# RoverWing-V1_1.net
KiCad netlist of a schematic drawn in EAGLE
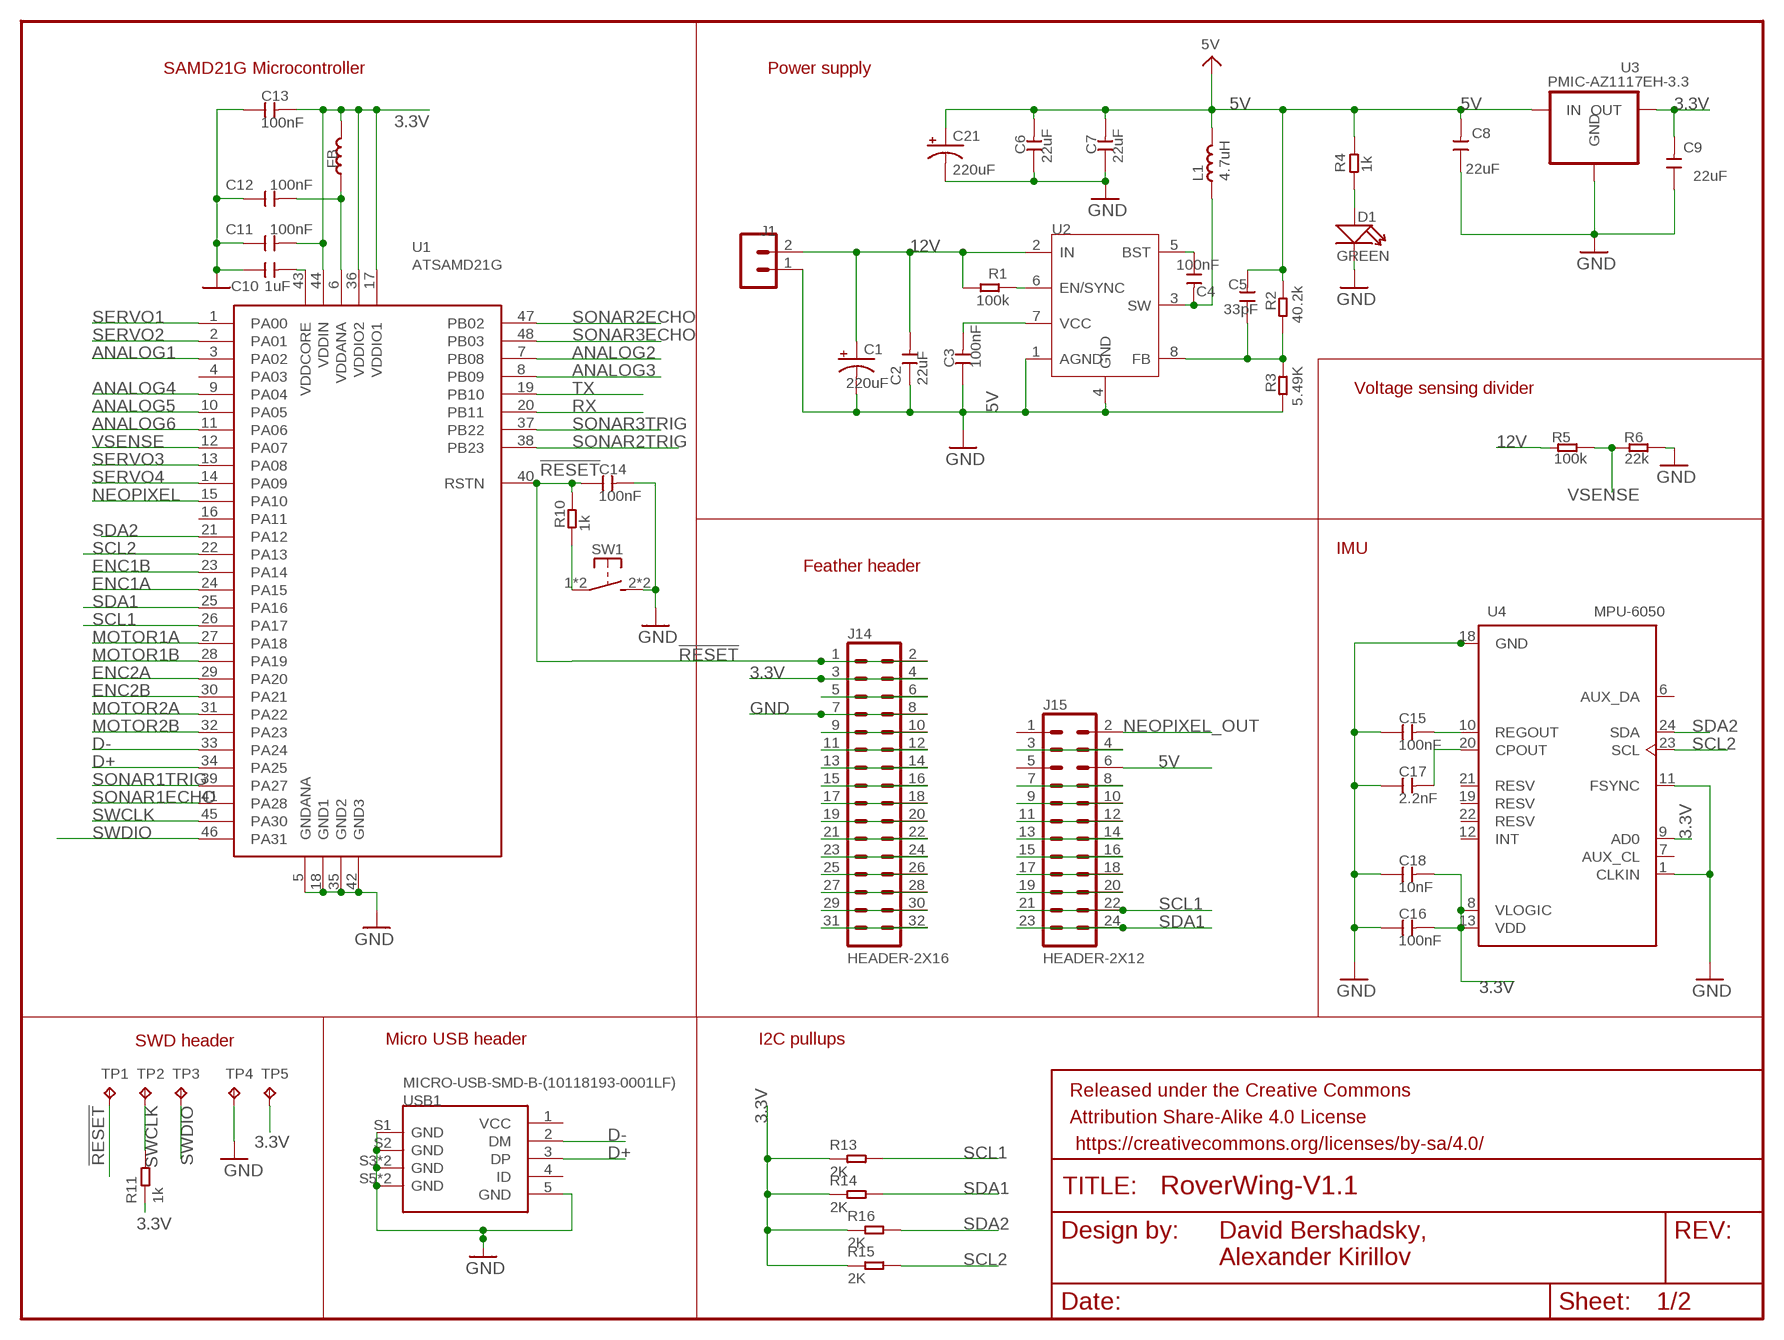
[diagram p0: schematic, sheet 1]
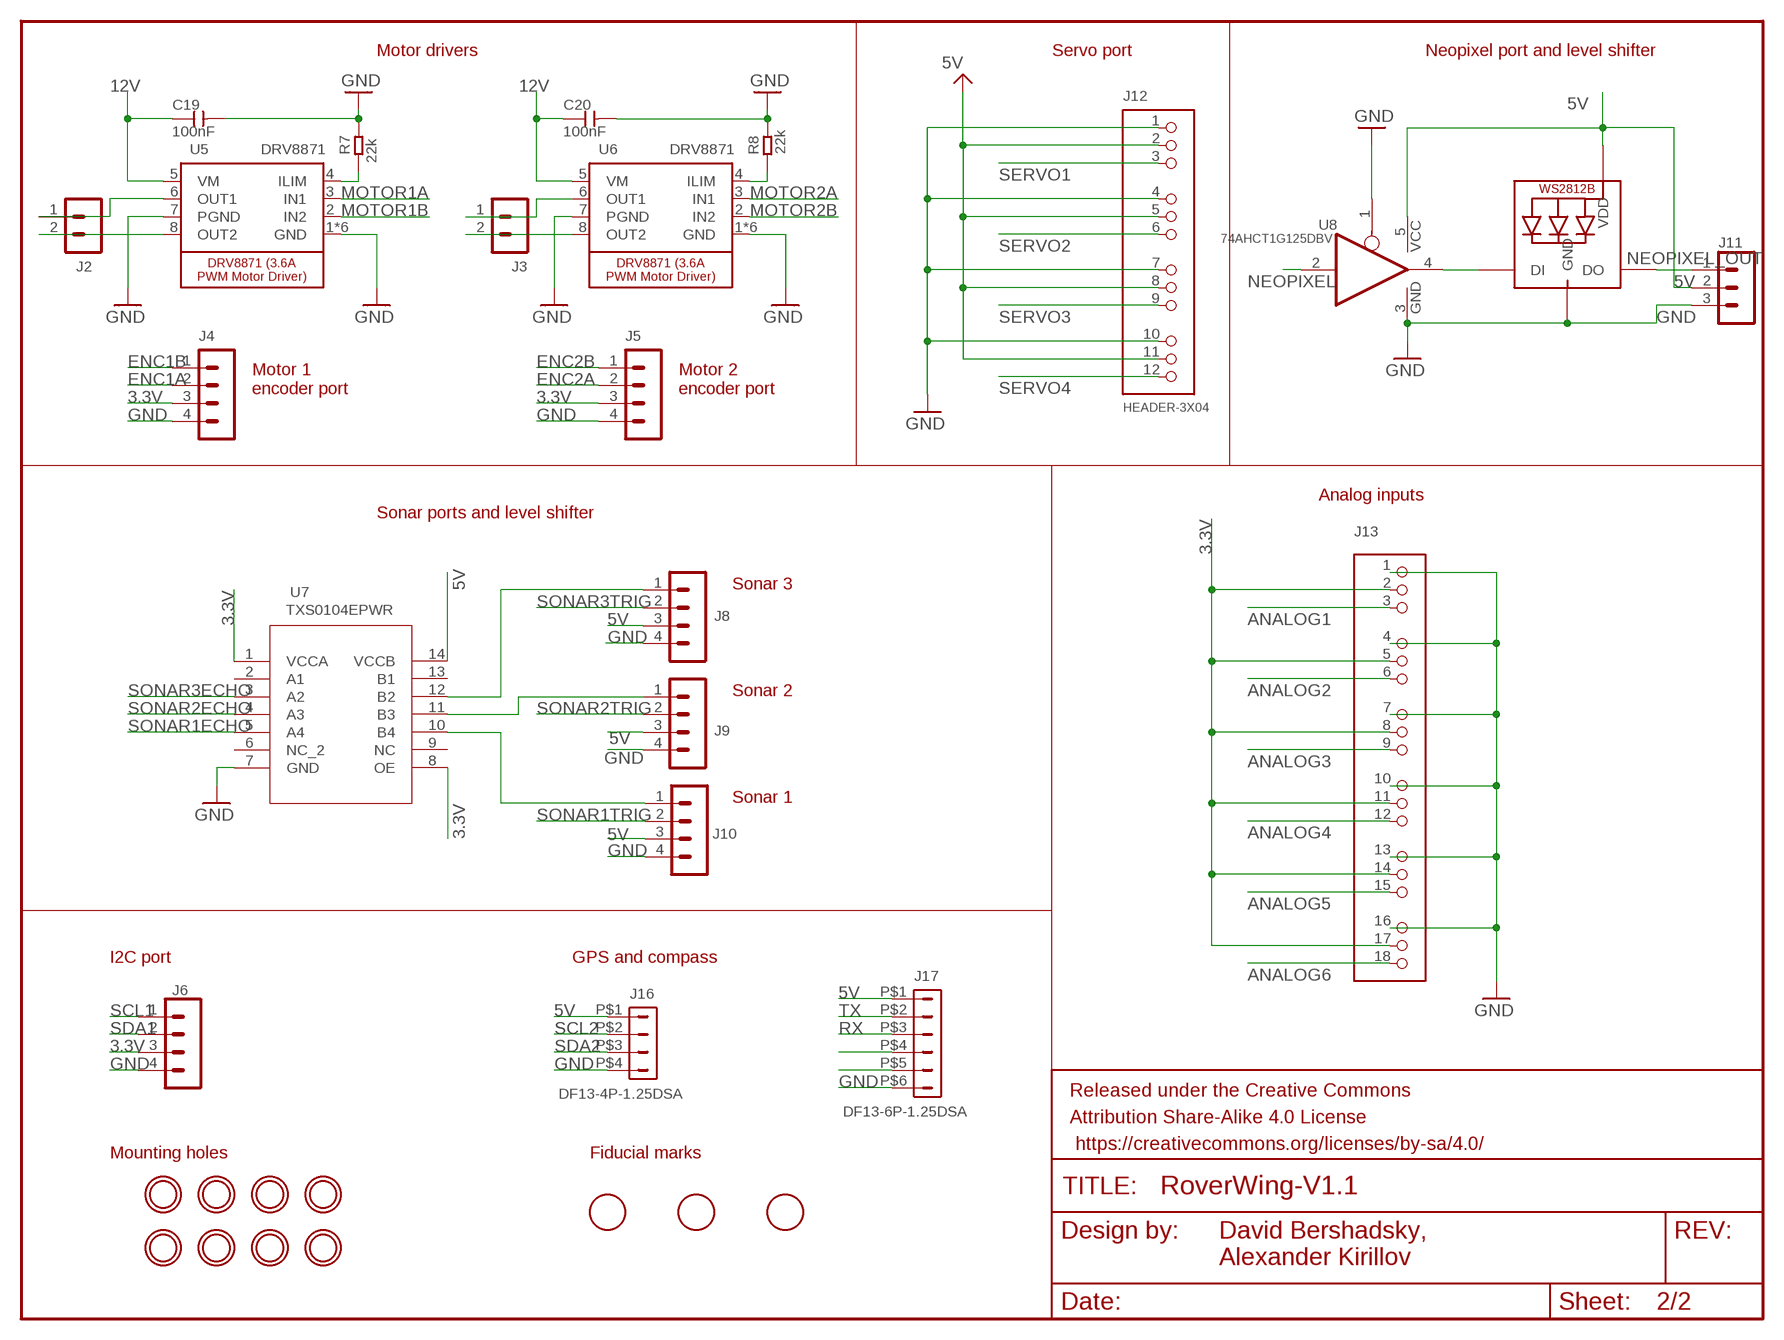
[diagram p1: schematic, sheet 2]

(export (version "E")
  (design (tool "Eeschema 10.0.6"))
  (components
    (comp (ref "C1")
      (value "220uF")
      (footprint "eagle-import:CAP-8X10.5")
      (libsource (lib "eagle-import") (part "CAP-POL-SMD-8X10.5"))
    )
    (comp (ref "C2")
      (value "22uF")
      (footprint "eagle-import:0805")
      (libsource (lib "eagle-import") (part "CAP-CERAMIC-SMD0805"))
    )
    (comp (ref "C3")
      (value "100nF")
      (footprint "eagle-import:0805")
      (libsource (lib "eagle-import") (part "CAP-CERAMIC-SMD0805"))
    )
    (comp (ref "C4")
      (value "100nF")
      (footprint "eagle-import:0805")
      (libsource (lib "eagle-import") (part "CAP-CERAMIC-SMD0805"))
    )
    (comp (ref "C5")
      (value "33pF")
      (footprint "eagle-import:0805")
      (libsource (lib "eagle-import") (part "CAP-CERAMIC-SMD0805"))
    )
    (comp (ref "C6")
      (value "22uF")
      (footprint "eagle-import:0805")
      (libsource (lib "eagle-import") (part "CAP-CERAMIC-SMD0805"))
    )
    (comp (ref "C7")
      (value "22uF")
      (footprint "eagle-import:0805")
      (libsource (lib "eagle-import") (part "CAP-CERAMIC-SMD0805"))
    )
    (comp (ref "C8")
      (value "22uF")
      (footprint "eagle-import:0805")
      (libsource (lib "eagle-import") (part "CAP-CERAMIC-SMD0805"))
    )
    (comp (ref "C9")
      (value "22uF")
      (footprint "eagle-import:0805")
      (libsource (lib "eagle-import") (part "CAP-CERAMIC-SMD0805"))
    )
    (comp (ref "C10")
      (value "1uF")
      (footprint "eagle-import:0805")
      (libsource (lib "eagle-import") (part "CAP-CERAMIC-SMD0805"))
    )
    (comp (ref "C11")
      (value "100nF")
      (footprint "eagle-import:0805")
      (libsource (lib "eagle-import") (part "CAP-CERAMIC-SMD0805"))
    )
    (comp (ref "C12")
      (value "100nF")
      (footprint "eagle-import:0805")
      (libsource (lib "eagle-import") (part "CAP-CERAMIC-SMD0805"))
    )
    (comp (ref "C13")
      (value "100nF")
      (footprint "eagle-import:0805")
      (libsource (lib "eagle-import") (part "CAP-CERAMIC-SMD0805"))
    )
    (comp (ref "C14")
      (value "100nF")
      (footprint "eagle-import:0805")
      (libsource (lib "eagle-import") (part "CAP-CERAMIC-SMD0805"))
    )
    (comp (ref "C15")
      (value "100nF")
      (footprint "eagle-import:0805")
      (libsource (lib "eagle-import") (part "CAP-CERAMIC-SMD0805"))
    )
    (comp (ref "C16")
      (value "100nF")
      (footprint "eagle-import:0805")
      (libsource (lib "eagle-import") (part "CAP-CERAMIC-SMD0805"))
    )
    (comp (ref "C17")
      (value "2.2nF")
      (footprint "eagle-import:0805")
      (libsource (lib "eagle-import") (part "CAP-CERAMIC-SMD0805"))
    )
    (comp (ref "C18")
      (value "10nF")
      (footprint "eagle-import:0805")
      (libsource (lib "eagle-import") (part "CAP-CERAMIC-SMD0805"))
    )
    (comp (ref "C21")
      (value "220uF")
      (footprint "eagle-import:CAP-6.3X5.4")
      (fields (field (name "PARTNO") "CS1E470M-CRE54 "))
      (libsource (lib "eagle-import") (part "CAP-POL-SMD-6.3X5.4"))
    )
    (comp (ref "D1")
      (value "GREEN")
      (footprint "eagle-import:LED-0805")
      (libsource (lib "eagle-import") (part "SMD-LED-0805"))
    )
    (comp (ref "FB")
      (value "330R-1500MA")
      (footprint "eagle-import:0805")
      (fields (field (name "PARTNO") "BLM21PG331SN1D"))
      (libsource (lib "eagle-import") (part "SMD-FERRITE-BEAD-330R-1500MA(0805)"))
    )
    (comp (ref "FRAME2")
      (value "FRAME-LETTERNO_PACKAGE")
      (footprint "eagle-import:DUMMY")
      (libsource (lib "eagle-import") (part "FRAME-LETTERNO_PACKAGE"))
    )
    (comp (ref "J1")
      (value "HEADER-VH")
      (footprint "eagle-import:B2P-VH")
      (fields (field (name "PARTNO") "B2P-VH(LF)(SN)  "))
      (libsource (lib "eagle-import") (part "HEADER-VH"))
    )
    (comp (ref "J14")
      (value "HEADER-2X16")
      (footprint "eagle-import:2X16")
      (libsource (lib "eagle-import") (part "HEADER-2X16"))
    )
    (comp (ref "J15")
      (value "HEADER-2X12")
      (footprint "eagle-import:2X12")
      (libsource (lib "eagle-import") (part "HEADER-2X12"))
    )
    (comp (ref "L1")
      (value "4.7uH")
      (footprint "eagle-import:IND_TDK_7.1X6.5")
      (fields (field (name "MANUFACTURER") "TDK") (field (name "PARTNO") "SPM6530T-4R7M "))
      (libsource (lib "eagle-import") (part "IND-TDK-SPM6530T"))
    )
    (comp (ref "R1")
      (value "100k")
      (footprint "eagle-import:0805")
      (libsource (lib "eagle-import") (part "RES-SMD-0805"))
    )
    (comp (ref "R2")
      (value "40.2k")
      (footprint "eagle-import:0805")
      (libsource (lib "eagle-import") (part "RES-SMD-0805"))
    )
    (comp (ref "R3")
      (value "5.49K")
      (footprint "eagle-import:0805")
      (libsource (lib "eagle-import") (part "RES-SMD-0805"))
    )
    (comp (ref "R4")
      (value "1k")
      (footprint "eagle-import:0805")
      (libsource (lib "eagle-import") (part "RES-SMD-0805"))
    )
    (comp (ref "R5")
      (value "100k")
      (footprint "eagle-import:0805")
      (libsource (lib "eagle-import") (part "RES-SMD-0805"))
    )
    (comp (ref "R6")
      (value "22k")
      (footprint "eagle-import:0805")
      (libsource (lib "eagle-import") (part "RES-SMD-0805"))
    )
    (comp (ref "R10")
      (value "1k")
      (footprint "eagle-import:0805")
      (libsource (lib "eagle-import") (part "RES-SMD-0805"))
    )
    (comp (ref "R11")
      (value "1k")
      (footprint "eagle-import:0805")
      (libsource (lib "eagle-import") (part "RES-SMD-0805"))
    )
    (comp (ref "R13")
      (value "2K")
      (footprint "eagle-import:R0603")
      (fields (field (name "MPN") "RC0603FR-071K8L"))
      (libsource (lib "eagle-import") (part "SMD-RES-1.8K-1%-1/10W(0603)"))
    )
    (comp (ref "R14")
      (value "2K")
      (footprint "eagle-import:R0603")
      (fields (field (name "MPN") "RC0603FR-071K8L"))
      (libsource (lib "eagle-import") (part "SMD-RES-1.8K-1%-1/10W(0603)"))
    )
    (comp (ref "R15")
      (value "2K")
      (footprint "eagle-import:R0603")
      (fields (field (name "MPN") "RC0603FR-071K8L"))
      (libsource (lib "eagle-import") (part "SMD-RES-1.8K-1%-1/10W(0603)"))
    )
    (comp (ref "R16")
      (value "2K")
      (footprint "eagle-import:R0603")
      (fields (field (name "MPN") "RC0603FR-071K8L"))
      (libsource (lib "eagle-import") (part "SMD-RES-1.8K-1%-1/10W(0603)"))
    )
    (comp (ref "SW1")
      (value "SW-TACTILE-4.5X4.5_SMD")
      (footprint "eagle-import:TL3305")
      (fields (field (name "MANUFACTURER") "BRIGHT") (field (name "PARTNO") "TSA453G38-250 "))
      (libsource (lib "eagle-import") (part "SW-TACTILE-4.5X4.5_SMD"))
    )
    (comp (ref "TP1")
      (value "TPTP15R")
      (footprint "eagle-import:TP15R")
      (libsource (lib "eagle-import") (part "TPTP15R"))
    )
    (comp (ref "TP2")
      (value "TPTP15R")
      (footprint "eagle-import:TP15R")
      (libsource (lib "eagle-import") (part "TPTP15R"))
    )
    (comp (ref "TP3")
      (value "TPTP15R")
      (footprint "eagle-import:TP15R")
      (libsource (lib "eagle-import") (part "TPTP15R"))
    )
    (comp (ref "TP4")
      (value "TPTP15R")
      (footprint "eagle-import:TP15R")
      (libsource (lib "eagle-import") (part "TPTP15R"))
    )
    (comp (ref "TP5")
      (value "TPTP15R")
      (footprint "eagle-import:TP15R")
      (libsource (lib "eagle-import") (part "TPTP15R"))
    )
    (comp (ref "U1")
      (value "ATSAMD21G")
      (footprint "eagle-import:TQFP-48-EDITED")
      (fields (field (name "MANUFACTURER") "Microchip Technology") (field (name "PARTNO") "ATSAMD21G18A-AU"))
      (libsource (lib "eagle-import") (part "ATSAMD21G"))
    )
    (comp (ref "U2")
      (value "MP2225")
      (footprint "eagle-import:SOT-23-8")
      (fields (field (name "MANUFACTURER") "Monolithic Power Systems") (field (name "PARTNO") "MP2225GJ"))
      (libsource (lib "eagle-import") (part "PMIC-MP2225"))
    )
    (comp (ref "U3")
      (value "PMIC-AZ1117EH-3.3")
      (footprint "eagle-import:SOT223")
      (fields (field (name "PARTNO") "AZ1117EH-3.3TRG1"))
      (libsource (lib "eagle-import") (part "PMIC-AZ1117EH-3.3"))
    )
    (comp (ref "U4")
      (value "MPU-6050")
      (footprint "eagle-import:QFN50P400X400X95-24N")
      (fields (field (name "MANUFACTURER") "TDK InvenSense"))
      (libsource (lib "eagle-import") (part "MPU-6050"))
    )
    (comp (ref "USB1")
      (value "MICRO-USB-SMD-B-(10118193-0001LF)")
      (footprint "eagle-import:MICRO-USB5+6P-SMD-0.65-B")
      (fields (field (name "MANUFACTURER") "Amphenol ICC") (field (name "PARTNO") "10118193-0001LF"))
      (libsource (lib "eagle-import") (part "MICRO-USB-SMD-B-(10118193-0001LF)"))
    )
    (comp (ref "C19")
      (value "100nF")
      (footprint "eagle-import:0805")
      (libsource (lib "eagle-import") (part "CAP-CERAMIC-SMD0805"))
    )
    (comp (ref "C20")
      (value "100nF")
      (footprint "eagle-import:0805")
      (libsource (lib "eagle-import") (part "CAP-CERAMIC-SMD0805"))
    )
    (comp (ref "D2")
      (value "WS2812B3535")
      (footprint "eagle-import:LED3535")
      (fields (field (name "MANUFACTURER") "Worldsemi") (field (name "PARTNO") "WS2812B-3535 "))
      (libsource (lib "eagle-import") (part "WS2812B3535"))
    )
    (comp (ref "FRAME1")
      (value "FRAME-LETTERNO_PACKAGE")
      (footprint "eagle-import:DUMMY")
      (libsource (lib "eagle-import") (part "FRAME-LETTERNO_PACKAGE"))
    )
    (comp (ref "J2")
      (value "HEADER-VH")
      (footprint "eagle-import:B2P-VH")
      (fields (field (name "PARTNO") "B2P-VH(LF)(SN)  "))
      (libsource (lib "eagle-import") (part "HEADER-VH"))
    )
    (comp (ref "J3")
      (value "HEADER-VH")
      (footprint "eagle-import:B2P-VH")
      (fields (field (name "PARTNO") "B2P-VH(LF)(SN)  "))
      (libsource (lib "eagle-import") (part "HEADER-VH"))
    )
    (comp (ref "J4")
      (value "HEADER-PH-4P")
      (footprint "eagle-import:B4B-PH-K")
      (fields (field (name "PARTNO") "B4B-PH-K-S(LF)(SN)"))
      (libsource (lib "eagle-import") (part "HEADER-PH-4P"))
    )
    (comp (ref "J5")
      (value "HEADER-PH-4P")
      (footprint "eagle-import:B4B-PH-K")
      (fields (field (name "PARTNO") "B4B-PH-K-S(LF)(SN)"))
      (libsource (lib "eagle-import") (part "HEADER-PH-4P"))
    )
    (comp (ref "J6")
      (value "HEADER-PH-4P")
      (footprint "eagle-import:B4B-PH-K")
      (fields (field (name "PARTNO") "B4B-PH-K-S(LF)(SN)"))
      (libsource (lib "eagle-import") (part "HEADER-PH-4P"))
    )
    (comp (ref "J8")
      (value "HEADER-PH-4P")
      (footprint "eagle-import:B4B-PH-K")
      (fields (field (name "PARTNO") "B4B-PH-K-S(LF)(SN)"))
      (libsource (lib "eagle-import") (part "HEADER-PH-4P"))
    )
    (comp (ref "J9")
      (value "HEADER-PH-4P")
      (footprint "eagle-import:B4B-PH-K")
      (fields (field (name "PARTNO") "B4B-PH-K-S(LF)(SN)"))
      (libsource (lib "eagle-import") (part "HEADER-PH-4P"))
    )
    (comp (ref "J10")
      (value "HEADER-PH-4P")
      (footprint "eagle-import:B4B-PH-K")
      (fields (field (name "PARTNO") "B4B-PH-K-S(LF)(SN)"))
      (libsource (lib "eagle-import") (part "HEADER-PH-4P"))
    )
    (comp (ref "J11")
      (value "HEADER-PH-3P")
      (footprint "eagle-import:B3B-PH-K")
      (fields (field (name "PARTNO") "B3B-PH-K-S(LF)(SN)"))
      (libsource (lib "eagle-import") (part "HEADER-PH-3P"))
    )
    (comp (ref "J12")
      (value "HEADER-3X04")
      (footprint "eagle-import:3X04")
      (libsource (lib "eagle-import") (part "HEADER-3X04"))
    )
    (comp (ref "J13")
      (value "HEADER-3X06\"")
      (footprint "eagle-import:3X06")
      (libsource (lib "eagle-import") (part "HEADER-3X06{dblquote}"))
    )
    (comp (ref "J16")
      (value "DF13-4P-1.25DSA")
      (footprint "eagle-import:DF13-4P-1.25DSA")
      (libsource (lib "eagle-import") (part "DF13-4P-1.25DSA"))
    )
    (comp (ref "J17")
      (value "DF13-6P-1.25DSA")
      (footprint "eagle-import:DF13-6P-1.25DSA")
      (libsource (lib "eagle-import") (part "DF13-6P-1.25DSA"))
    )
    (comp (ref "R7")
      (value "22k")
      (footprint "eagle-import:0805")
      (libsource (lib "eagle-import") (part "RES-SMD-0805"))
    )
    (comp (ref "R8")
      (value "22k")
      (footprint "eagle-import:0805")
      (libsource (lib "eagle-import") (part "RES-SMD-0805"))
    )
    (comp (ref "U$3")
      (value "MOUNTINGHOLE3.0_NPH")
      (footprint "eagle-import:MOUNTINGHOLE_3.0_NPH")
      (libsource (lib "eagle-import") (part "MOUNTINGHOLE3.0_NPH"))
    )
    (comp (ref "U$4")
      (value "MOUNTINGHOLE3.0_NPH")
      (footprint "eagle-import:MOUNTINGHOLE_3.0_NPH")
      (libsource (lib "eagle-import") (part "MOUNTINGHOLE3.0_NPH"))
    )
    (comp (ref "U$11")
      (value "FIDUCIAL")
      (footprint "eagle-import:FIDUCIAL_1MM")
      (libsource (lib "eagle-import") (part "FIDUCIAL"))
    )
    (comp (ref "U$13")
      (value "FIDUCIAL")
      (footprint "eagle-import:FIDUCIAL_1MM")
      (libsource (lib "eagle-import") (part "FIDUCIAL"))
    )
    (comp (ref "U$14")
      (value "MOUNTINGHOLE3.0_NPH")
      (footprint "eagle-import:MOUNTINGHOLE_3.0_NPH")
      (libsource (lib "eagle-import") (part "MOUNTINGHOLE3.0_NPH"))
    )
    (comp (ref "U$15")
      (value "MOUNTINGHOLE3.0_NPH")
      (footprint "eagle-import:MOUNTINGHOLE_3.0_NPH")
      (libsource (lib "eagle-import") (part "MOUNTINGHOLE3.0_NPH"))
    )
    (comp (ref "U$17")
      (value "FIDUCIAL")
      (footprint "eagle-import:FIDUCIAL_1MM")
      (libsource (lib "eagle-import") (part "FIDUCIAL"))
    )
    (comp (ref "U$24")
      (value "MOUNTINGHOLE3.0_NPH")
      (footprint "eagle-import:MOUNTINGHOLE_3.0_NPH")
      (libsource (lib "eagle-import") (part "MOUNTINGHOLE3.0_NPH"))
    )
    (comp (ref "U$25")
      (value "MOUNTINGHOLE3.0_NPH")
      (footprint "eagle-import:MOUNTINGHOLE_3.0_NPH")
      (libsource (lib "eagle-import") (part "MOUNTINGHOLE3.0_NPH"))
    )
    (comp (ref "U$26")
      (value "MOUNTINGHOLE3.0_NPH")
      (footprint "eagle-import:MOUNTINGHOLE_3.0_NPH")
      (libsource (lib "eagle-import") (part "MOUNTINGHOLE3.0_NPH"))
    )
    (comp (ref "U$27")
      (value "MOUNTINGHOLE3.0_NPH")
      (footprint "eagle-import:MOUNTINGHOLE_3.0_NPH")
      (libsource (lib "eagle-import") (part "MOUNTINGHOLE3.0_NPH"))
    )
    (comp (ref "U5")
      (value "DRV8871")
      (footprint "eagle-import:HSOP8")
      (fields (field (name "MANUFACTURER") "TEXAS INSTRUMENTS") (field (name "PARTNO") "DRV8871DDAR"))
      (libsource (lib "eagle-import") (part "DRV8871"))
    )
    (comp (ref "U6")
      (value "DRV8871")
      (footprint "eagle-import:HSOP8")
      (fields (field (name "MANUFACTURER") "TEXAS INSTRUMENTS") (field (name "PARTNO") "DRV8871DDAR"))
      (libsource (lib "eagle-import") (part "DRV8871"))
    )
    (comp (ref "U7")
      (value "TXS0104EPWR")
      (footprint "eagle-import:PW14")
      (fields (field (name "MANUFACTURER") "Texas Instruments"))
      (libsource (lib "eagle-import") (part "TXS0104EPWR"))
    )
    (comp (ref "U8")
      (value "74AHCT1G125DBV")
      (footprint "eagle-import:SOT23-5")
      (fields (field (name "PARTNO") "SN74AHCT1G125DBVR"))
      (libsource (lib "eagle-import") (part "741G125DBVAHCT"))
    )
  )
  (nets
    (net (code "1") (name "3.3V") (class "Default")
      (node (ref "C11") (pin "2") (pinfunction "2_2") (pintype "passive"))
      (node (ref "C13") (pin "2") (pinfunction "2_2") (pintype "passive"))
      (node (ref "C16") (pin "2") (pinfunction "2_2") (pintype "passive"))
      (node (ref "C18") (pin "2") (pinfunction "2_2") (pintype "passive"))
      (node (ref "C9") (pin "2") (pinfunction "2_2") (pintype "passive"))
      (node (ref "FB") (pin "2") (pinfunction "2_2") (pintype "passive"))
      (node (ref "J13") (pin "11") (pinfunction "11_11") (pintype "passive"))
      (node (ref "J13") (pin "14") (pinfunction "14_14") (pintype "passive"))
      (node (ref "J13") (pin "17") (pinfunction "17_17") (pintype "passive"))
      (node (ref "J13") (pin "2") (pinfunction "2_2") (pintype "passive"))
      (node (ref "J13") (pin "5") (pinfunction "5_5") (pintype "passive"))
      (node (ref "J13") (pin "8") (pinfunction "8_8") (pintype "passive"))
      (node (ref "J14") (pin "3") (pinfunction "3_3") (pintype "passive"))
      (node (ref "J14") (pin "4") (pinfunction "4_4") (pintype "passive"))
      (node (ref "J4") (pin "3") (pinfunction "3_3") (pintype "passive"))
      (node (ref "J5") (pin "3") (pinfunction "3_3") (pintype "passive"))
      (node (ref "J6") (pin "3") (pinfunction "3_3") (pintype "passive"))
      (node (ref "R11") (pin "1") (pinfunction "1_1") (pintype "passive"))
      (node (ref "R13") (pin "1") (pinfunction "1_1") (pintype "passive"))
      (node (ref "R14") (pin "1") (pinfunction "1_1") (pintype "passive"))
      (node (ref "R15") (pin "1") (pinfunction "1_1") (pintype "passive"))
      (node (ref "R16") (pin "1") (pinfunction "1_1") (pintype "passive"))
      (node (ref "TP5") (pin "TP") (pinfunction "TP_TP") (pintype "input"))
      (node (ref "U1") (pin "17") (pinfunction "VDDIO1_17") (pintype "power_in"))
      (node (ref "U1") (pin "36") (pinfunction "VDDIO2_36") (pintype "power_in"))
      (node (ref "U1") (pin "44") (pinfunction "VDDIN_44") (pintype "power_in"))
      (node (ref "U3") (pin "2") (pinfunction "OUT_2") (pintype "output"))
      (node (ref "U3") (pin "4") (pinfunction "OUT_4") (pintype "output"))
      (node (ref "U4") (pin "13") (pinfunction "VDD_13") (pintype "power_in"))
      (node (ref "U4") (pin "8") (pinfunction "VLOGIC_8") (pintype "power_in"))
      (node (ref "U4") (pin "9") (pinfunction "AD0_9") (pintype "input"))
      (node (ref "U7") (pin "1") (pinfunction "VCCA_1") (pintype "power_in"))
      (node (ref "U7") (pin "8") (pinfunction "OE_8") (pintype "output"))
    )
    (net (code "2") (name "5V") (class "Default")
      (node (ref "C21") (pin "+") (pinfunction "+_+") (pintype "passive"))
      (node (ref "C5") (pin "2") (pinfunction "2_2") (pintype "passive"))
      (node (ref "C6") (pin "2") (pinfunction "2_2") (pintype "passive"))
      (node (ref "C7") (pin "2") (pinfunction "2_2") (pintype "passive"))
      (node (ref "C8") (pin "2") (pinfunction "2_2") (pintype "passive"))
      (node (ref "D2") (pin "3") (pinfunction "VDD_3") (pintype "power_in"))
      (node (ref "J10") (pin "3") (pinfunction "3_3") (pintype "passive"))
      (node (ref "J11") (pin "2") (pinfunction "2_2") (pintype "passive"))
      (node (ref "J12") (pin "11") (pinfunction "11_11") (pintype "passive"))
      (node (ref "J12") (pin "2") (pinfunction "2_2") (pintype "passive"))
      (node (ref "J12") (pin "5") (pinfunction "5_5") (pintype "passive"))
      (node (ref "J12") (pin "8") (pinfunction "8_8") (pintype "passive"))
      (node (ref "J15") (pin "6") (pinfunction "6_6") (pintype "passive"))
      (node (ref "J16") (pin "P$1") (pinfunction "1_P$1") (pintype "passive"))
      (node (ref "J17") (pin "P$1") (pinfunction "1_P$1") (pintype "passive"))
      (node (ref "J8") (pin "3") (pinfunction "3_3") (pintype "passive"))
      (node (ref "J9") (pin "3") (pinfunction "3_3") (pintype "passive"))
      (node (ref "L1") (pin "2") (pinfunction "2_2") (pintype "passive"))
      (node (ref "R2") (pin "1") (pinfunction "1_1") (pintype "passive"))
      (node (ref "R4") (pin "2") (pinfunction "2_2") (pintype "passive"))
      (node (ref "U3") (pin "3") (pinfunction "IN_3") (pintype "input"))
      (node (ref "U7") (pin "14") (pinfunction "VCCB_14") (pintype "power_in"))
      (node (ref "U8") (pin "5") (pinfunction "VCC_5") (pintype "power_in"))
    )
    (net (code "3") (name "12V") (class "Default")
      (node (ref "C1") (pin "+") (pinfunction "+_+") (pintype "passive"))
      (node (ref "C19") (pin "1") (pinfunction "1_1") (pintype "passive"))
      (node (ref "C2") (pin "2") (pinfunction "2_2") (pintype "passive"))
      (node (ref "C20") (pin "1") (pinfunction "1_1") (pintype "passive"))
      (node (ref "J1") (pin "2") (pinfunction "2_2") (pintype "passive"))
      (node (ref "R1") (pin "2") (pinfunction "2_2") (pintype "passive"))
      (node (ref "R5") (pin "2") (pinfunction "2_2") (pintype "passive"))
      (node (ref "U2") (pin "2") (pinfunction "IN_2") (pintype "bidirectional"))
      (node (ref "U5") (pin "5") (pinfunction "VM_5") (pintype "power_in"))
      (node (ref "U6") (pin "5") (pinfunction "VM_5") (pintype "power_in"))
    )
    (net (code "4") (name "ANALOG1") (class "Default")
      (node (ref "J13") (pin "3") (pinfunction "3_3") (pintype "passive"))
      (node (ref "U1") (pin "3") (pinfunction "PA02_3") (pintype "bidirectional"))
    )
    (net (code "5") (name "ANALOG2") (class "Default")
      (node (ref "J13") (pin "6") (pinfunction "6_6") (pintype "passive"))
      (node (ref "U1") (pin "7") (pinfunction "PB08_7") (pintype "bidirectional"))
    )
    (net (code "6") (name "ANALOG3") (class "Default")
      (node (ref "J13") (pin "9") (pinfunction "9_9") (pintype "passive"))
      (node (ref "U1") (pin "8") (pinfunction "PB09_8") (pintype "bidirectional"))
    )
    (net (code "7") (name "ANALOG4") (class "Default")
      (node (ref "J13") (pin "12") (pinfunction "12_12") (pintype "passive"))
      (node (ref "U1") (pin "9") (pinfunction "PA04_9") (pintype "bidirectional"))
    )
    (net (code "8") (name "ANALOG5") (class "Default")
      (node (ref "J13") (pin "15") (pinfunction "15_15") (pintype "passive"))
      (node (ref "U1") (pin "10") (pinfunction "PA05_10") (pintype "bidirectional"))
    )
    (net (code "9") (name "ANALOG6") (class "Default")
      (node (ref "J13") (pin "18") (pinfunction "18_18") (pintype "passive"))
      (node (ref "U1") (pin "11") (pinfunction "PA06_11") (pintype "bidirectional"))
    )
    (net (code "10") (name "D+") (class "Default")
      (node (ref "U1") (pin "34") (pinfunction "PA25_34") (pintype "bidirectional"))
      (node (ref "USB1") (pin "3") (pinfunction "DP_3") (pintype "bidirectional"))
    )
    (net (code "11") (name "D-") (class "Default")
      (node (ref "U1") (pin "33") (pinfunction "PA24_33") (pintype "bidirectional"))
      (node (ref "USB1") (pin "2") (pinfunction "DM_2") (pintype "bidirectional"))
    )
    (net (code "12") (name "ENC1A") (class "Default")
      (node (ref "J4") (pin "2") (pinfunction "2_2") (pintype "passive"))
      (node (ref "U1") (pin "24") (pinfunction "PA15_24") (pintype "bidirectional"))
    )
    (net (code "13") (name "ENC1B") (class "Default")
      (node (ref "J4") (pin "1") (pinfunction "1_1") (pintype "passive"))
      (node (ref "U1") (pin "23") (pinfunction "PA14_23") (pintype "bidirectional"))
    )
    (net (code "14") (name "ENC2A") (class "Default")
      (node (ref "J5") (pin "2") (pinfunction "2_2") (pintype "passive"))
      (node (ref "U1") (pin "29") (pinfunction "PA20_29") (pintype "bidirectional"))
    )
    (net (code "15") (name "ENC2B") (class "Default")
      (node (ref "J5") (pin "1") (pinfunction "1_1") (pintype "passive"))
      (node (ref "U1") (pin "30") (pinfunction "PA21_30") (pintype "bidirectional"))
    )
    (net (code "16") (name "GND") (class "Default")
      (node (ref "C1") (pin "-") (pinfunction "-_-") (pintype "passive"))
      (node (ref "C10") (pin "1") (pinfunction "1_1") (pintype "passive"))
      (node (ref "C11") (pin "1") (pinfunction "1_1") (pintype "passive"))
      (node (ref "C12") (pin "1") (pinfunction "1_1") (pintype "passive"))
      (node (ref "C13") (pin "1") (pinfunction "1_1") (pintype "passive"))
      (node (ref "C14") (pin "2") (pinfunction "2_2") (pintype "passive"))
      (node (ref "C15") (pin "1") (pinfunction "1_1") (pintype "passive"))
      (node (ref "C16") (pin "1") (pinfunction "1_1") (pintype "passive"))
      (node (ref "C17") (pin "1") (pinfunction "1_1") (pintype "passive"))
      (node (ref "C18") (pin "1") (pinfunction "1_1") (pintype "passive"))
      (node (ref "C19") (pin "2") (pinfunction "2_2") (pintype "passive"))
      (node (ref "C2") (pin "1") (pinfunction "1_1") (pintype "passive"))
      (node (ref "C20") (pin "2") (pinfunction "2_2") (pintype "passive"))
      (node (ref "C21") (pin "-") (pinfunction "-_-") (pintype "passive"))
      (node (ref "C3") (pin "1") (pinfunction "1_1") (pintype "passive"))
      (node (ref "C6") (pin "1") (pinfunction "1_1") (pintype "passive"))
      (node (ref "C7") (pin "1") (pinfunction "1_1") (pintype "passive"))
      (node (ref "C8") (pin "1") (pinfunction "1_1") (pintype "passive"))
      (node (ref "C9") (pin "1") (pinfunction "1_1") (pintype "passive"))
      (node (ref "D1") (pin "-") (pinfunction "-_-") (pintype "passive"))
      (node (ref "D2") (pin "1") (pinfunction "GND_1") (pintype "power_in"))
      (node (ref "J1") (pin "1") (pinfunction "1_1") (pintype "passive"))
      (node (ref "J10") (pin "4") (pinfunction "4_4") (pintype "passive"))
      (node (ref "J11") (pin "3") (pinfunction "3_3") (pintype "passive"))
      (node (ref "J12") (pin "1") (pinfunction "1_1") (pintype "passive"))
      (node (ref "J12") (pin "10") (pinfunction "10_10") (pintype "passive"))
      (node (ref "J12") (pin "4") (pinfunction "4_4") (pintype "passive"))
      (node (ref "J12") (pin "7") (pinfunction "7_7") (pintype "passive"))
      (node (ref "J13") (pin "1") (pinfunction "1_1") (pintype "passive"))
      (node (ref "J13") (pin "10") (pinfunction "10_10") (pintype "passive"))
      (node (ref "J13") (pin "13") (pinfunction "13_13") (pintype "passive"))
      (node (ref "J13") (pin "16") (pinfunction "16_16") (pintype "passive"))
      (node (ref "J13") (pin "4") (pinfunction "4_4") (pintype "passive"))
      (node (ref "J13") (pin "7") (pinfunction "7_7") (pintype "passive"))
      (node (ref "J14") (pin "7") (pinfunction "7_7") (pintype "passive"))
      (node (ref "J14") (pin "8") (pinfunction "8_8") (pintype "passive"))
      (node (ref "J16") (pin "P$4") (pinfunction "4_P$4") (pintype "passive"))
      (node (ref "J17") (pin "P$6") (pinfunction "6_P$6") (pintype "passive"))
      (node (ref "J4") (pin "4") (pinfunction "4_4") (pintype "passive"))
      (node (ref "J5") (pin "4") (pinfunction "4_4") (pintype "passive"))
      (node (ref "J6") (pin "4") (pinfunction "4_4") (pintype "passive"))
      (node (ref "J8") (pin "4") (pinfunction "4_4") (pintype "passive"))
      (node (ref "J9") (pin "4") (pinfunction "4_4") (pintype "passive"))
      (node (ref "R3") (pin "2") (pinfunction "2_2") (pintype "passive"))
      (node (ref "R6") (pin "2") (pinfunction "2_2") (pintype "passive"))
      (node (ref "R7") (pin "2") (pinfunction "2_2") (pintype "passive"))
      (node (ref "R8") (pin "2") (pinfunction "2_2") (pintype "passive"))
      (node (ref "SW1") (pin "2") (pinfunction "S1_2") (pintype "passive"))
      (node (ref "SW1") (pin "3") (pinfunction "S1_3") (pintype "passive"))
      (node (ref "TP4") (pin "TP") (pinfunction "TP_TP") (pintype "input"))
      (node (ref "U1") (pin "18") (pinfunction "GND1_18") (pintype "power_in"))
      (node (ref "U1") (pin "35") (pinfunction "GND2_35") (pintype "power_in"))
      (node (ref "U1") (pin "42") (pinfunction "GND3_42") (pintype "power_in"))
      (node (ref "U1") (pin "5") (pinfunction "GNDANA_5") (pintype "power_in"))
      (node (ref "U2") (pin "1") (pinfunction "AGND_1") (pintype "bidirectional"))
      (node (ref "U2") (pin "4") (pinfunction "GND_4") (pintype "bidirectional"))
      (node (ref "U3") (pin "1") (pinfunction "GND_1") (pintype "power_in"))
      (node (ref "U4") (pin "1") (pinfunction "CLKIN_1") (pintype "input"))
      (node (ref "U4") (pin "11") (pinfunction "FSYNC_11") (pintype "input"))
      (node (ref "U4") (pin "18") (pinfunction "GND_18") (pintype "power_in"))
      (node (ref "U5") (pin "1") (pinfunction "GND_1") (pintype "power_in"))
      (node (ref "U5") (pin "7") (pinfunction "PGND_7") (pintype "power_in"))
      (node (ref "U5") (pin "GND") (pinfunction "GND_GND") (pintype "power_in"))
      (node (ref "U5") (pin "P$1") (pinfunction "GND_P$1") (pintype "power_in"))
      (node (ref "U5") (pin "P$2") (pinfunction "GND_P$2") (pintype "power_in"))
      (node (ref "U5") (pin "P$3") (pinfunction "GND_P$3") (pintype "power_in"))
      (node (ref "U5") (pin "P$4") (pinfunction "GND_P$4") (pintype "power_in"))
      (node (ref "U6") (pin "1") (pinfunction "GND_1") (pintype "power_in"))
      (node (ref "U6") (pin "7") (pinfunction "PGND_7") (pintype "power_in"))
      (node (ref "U6") (pin "GND") (pinfunction "GND_GND") (pintype "power_in"))
      (node (ref "U6") (pin "P$1") (pinfunction "GND_P$1") (pintype "power_in"))
      (node (ref "U6") (pin "P$2") (pinfunction "GND_P$2") (pintype "power_in"))
      (node (ref "U6") (pin "P$3") (pinfunction "GND_P$3") (pintype "power_in"))
      (node (ref "U6") (pin "P$4") (pinfunction "GND_P$4") (pintype "power_in"))
      (node (ref "U7") (pin "7") (pinfunction "GND_7") (pintype "power_in"))
      (node (ref "U8") (pin "1") (pinfunction "OE_1") (pintype "input"))
      (node (ref "U8") (pin "3") (pinfunction "GND_3") (pintype "power_in"))
      (node (ref "USB1") (pin "5") (pinfunction "GND_5") (pintype "bidirectional"))
      (node (ref "USB1") (pin "S1") (pinfunction "GND_S1") (pintype "bidirectional"))
      (node (ref "USB1") (pin "S2") (pinfunction "GND_S2") (pintype "bidirectional"))
      (node (ref "USB1") (pin "S3") (pinfunction "GND_S3") (pintype "bidirectional"))
      (node (ref "USB1") (pin "S4") (pinfunction "GND_S4") (pintype "bidirectional"))
      (node (ref "USB1") (pin "S5") (pinfunction "GND_S5") (pintype "bidirectional"))
      (node (ref "USB1") (pin "S6") (pinfunction "GND_S6") (pintype "bidirectional"))
    )
    (net (code "17") (name "MOTOR1A") (class "Default")
      (node (ref "U1") (pin "27") (pinfunction "PA18_27") (pintype "bidirectional"))
      (node (ref "U5") (pin "3") (pinfunction "IN1_3") (pintype "input"))
    )
    (net (code "18") (name "MOTOR1B") (class "Default")
      (node (ref "U1") (pin "28") (pinfunction "PA19_28") (pintype "bidirectional"))
      (node (ref "U5") (pin "2") (pinfunction "IN2_2") (pintype "input"))
    )
    (net (code "19") (name "MOTOR2A") (class "Default")
      (node (ref "U1") (pin "31") (pinfunction "PA22_31") (pintype "bidirectional"))
      (node (ref "U6") (pin "3") (pinfunction "IN1_3") (pintype "input"))
    )
    (net (code "20") (name "MOTOR2B") (class "Default")
      (node (ref "U1") (pin "32") (pinfunction "PA23_32") (pintype "bidirectional"))
      (node (ref "U6") (pin "2") (pinfunction "IN2_2") (pintype "input"))
    )
    (net (code "21") (name "NEOPIXEL") (class "Default")
      (node (ref "U1") (pin "15") (pinfunction "PA10_15") (pintype "bidirectional"))
      (node (ref "U8") (pin "2") (pinfunction "I_2") (pintype "input"))
    )
    (net (code "22") (name "NEOPIXEL_OUT") (class "Default")
      (node (ref "D2") (pin "4") (pinfunction "DO_4") (pintype "output"))
      (node (ref "J11") (pin "1") (pinfunction "1_1") (pintype "passive"))
      (node (ref "J15") (pin "2") (pinfunction "2_2") (pintype "passive"))
    )
    (net (code "23") (name "Net-(D1-Pad+)") (class "Default")
      (node (ref "D1") (pin "+") (pinfunction "+_+") (pintype "passive"))
      (node (ref "R4") (pin "1") (pinfunction "1_1") (pintype "passive"))
    )
    (net (code "24") (name "Net-(D2-DI)") (class "Default")
      (node (ref "D2") (pin "2") (pinfunction "DI_2") (pintype "input"))
      (node (ref "U8") (pin "4") (pinfunction "O_4") (pintype "tri_state"))
    )
    (net (code "25") (name "Net-(J14-Pad5)") (class "Default")
      (node (ref "J14") (pin "5") (pinfunction "5_5") (pintype "passive"))
      (node (ref "J14") (pin "6") (pinfunction "6_6") (pintype "passive"))
    )
    (net (code "26") (name "Net-(J14-Pad10)") (class "Default")
      (node (ref "J14") (pin "10") (pinfunction "10_10") (pintype "passive"))
      (node (ref "J14") (pin "9") (pinfunction "9_9") (pintype "passive"))
    )
    (net (code "27") (name "Net-(J14-Pad11)") (class "Default")
      (node (ref "J14") (pin "11") (pinfunction "11_11") (pintype "passive"))
      (node (ref "J14") (pin "12") (pinfunction "12_12") (pintype "passive"))
    )
    (net (code "28") (name "Net-(J14-Pad13)") (class "Default")
      (node (ref "J14") (pin "13") (pinfunction "13_13") (pintype "passive"))
      (node (ref "J14") (pin "14") (pinfunction "14_14") (pintype "passive"))
    )
    (net (code "29") (name "Net-(J14-Pad15)") (class "Default")
      (node (ref "J14") (pin "15") (pinfunction "15_15") (pintype "passive"))
      (node (ref "J14") (pin "16") (pinfunction "16_16") (pintype "passive"))
    )
    (net (code "30") (name "Net-(J14-Pad17)") (class "Default")
      (node (ref "J14") (pin "17") (pinfunction "17_17") (pintype "passive"))
      (node (ref "J14") (pin "18") (pinfunction "18_18") (pintype "passive"))
    )
    (net (code "31") (name "Net-(J14-Pad19)") (class "Default")
      (node (ref "J14") (pin "19") (pinfunction "19_19") (pintype "passive"))
      (node (ref "J14") (pin "20") (pinfunction "20_20") (pintype "passive"))
    )
    (net (code "32") (name "Net-(J14-Pad21)") (class "Default")
      (node (ref "J14") (pin "21") (pinfunction "21_21") (pintype "passive"))
      (node (ref "J14") (pin "22") (pinfunction "22_22") (pintype "passive"))
    )
    (net (code "33") (name "Net-(J14-Pad23)") (class "Default")
      (node (ref "J14") (pin "23") (pinfunction "23_23") (pintype "passive"))
      (node (ref "J14") (pin "24") (pinfunction "24_24") (pintype "passive"))
    )
    (net (code "34") (name "Net-(J14-Pad25)") (class "Default")
      (node (ref "J14") (pin "25") (pinfunction "25_25") (pintype "passive"))
      (node (ref "J14") (pin "26") (pinfunction "26_26") (pintype "passive"))
    )
    (net (code "35") (name "Net-(J14-Pad27)") (class "Default")
      (node (ref "J14") (pin "27") (pinfunction "27_27") (pintype "passive"))
      (node (ref "J14") (pin "28") (pinfunction "28_28") (pintype "passive"))
    )
    (net (code "36") (name "Net-(J14-Pad29)") (class "Default")
      (node (ref "J14") (pin "29") (pinfunction "29_29") (pintype "passive"))
      (node (ref "J14") (pin "30") (pinfunction "30_30") (pintype "passive"))
    )
    (net (code "37") (name "Net-(J14-Pad31)") (class "Default")
      (node (ref "J14") (pin "31") (pinfunction "31_31") (pintype "passive"))
      (node (ref "J14") (pin "32") (pinfunction "32_32") (pintype "passive"))
    )
    (net (code "38") (name "Net-(J15-Pad3)") (class "Default")
      (node (ref "J15") (pin "3") (pinfunction "3_3") (pintype "passive"))
      (node (ref "J15") (pin "4") (pinfunction "4_4") (pintype "passive"))
    )
    (net (code "39") (name "Net-(J15-Pad7)") (class "Default")
      (node (ref "J15") (pin "7") (pinfunction "7_7") (pintype "passive"))
      (node (ref "J15") (pin "8") (pinfunction "8_8") (pintype "passive"))
    )
    (net (code "40") (name "Net-(J15-Pad10)") (class "Default")
      (node (ref "J15") (pin "10") (pinfunction "10_10") (pintype "passive"))
      (node (ref "J15") (pin "9") (pinfunction "9_9") (pintype "passive"))
    )
    (net (code "41") (name "Net-(J15-Pad11)") (class "Default")
      (node (ref "J15") (pin "11") (pinfunction "11_11") (pintype "passive"))
      (node (ref "J15") (pin "12") (pinfunction "12_12") (pintype "passive"))
    )
    (net (code "42") (name "Net-(J15-Pad13)") (class "Default")
      (node (ref "J15") (pin "13") (pinfunction "13_13") (pintype "passive"))
      (node (ref "J15") (pin "14") (pinfunction "14_14") (pintype "passive"))
    )
    (net (code "43") (name "Net-(J15-Pad15)") (class "Default")
      (node (ref "J15") (pin "15") (pinfunction "15_15") (pintype "passive"))
      (node (ref "J15") (pin "16") (pinfunction "16_16") (pintype "passive"))
    )
    (net (code "44") (name "Net-(J15-Pad17)") (class "Default")
      (node (ref "J15") (pin "17") (pinfunction "17_17") (pintype "passive"))
      (node (ref "J15") (pin "18") (pinfunction "18_18") (pintype "passive"))
    )
    (net (code "45") (name "Net-(J15-Pad19)") (class "Default")
      (node (ref "J15") (pin "19") (pinfunction "19_19") (pintype "passive"))
      (node (ref "J15") (pin "20") (pinfunction "20_20") (pintype "passive"))
    )
    (net (code "46") (name "Net-(R10-Pad1)") (class "Default")
      (node (ref "R10") (pin "1") (pinfunction "1_1") (pintype "passive"))
      (node (ref "SW1") (pin "1") (pinfunction "P1_1") (pintype "passive"))
      (node (ref "SW1") (pin "4") (pinfunction "P1_4") (pintype "passive"))
    )
    (net (code "47") (name "Net-(U1-VDDANA)") (class "Default")
      (node (ref "C12") (pin "2") (pinfunction "2_2") (pintype "passive"))
      (node (ref "FB") (pin "1") (pinfunction "1_1") (pintype "passive"))
      (node (ref "U1") (pin "6") (pinfunction "VDDANA_6") (pintype "power_in"))
    )
    (net (code "48") (name "Net-(U1-VDDCORE)") (class "Default")
      (node (ref "C10") (pin "2") (pinfunction "2_2") (pintype "passive"))
      (node (ref "U1") (pin "43") (pinfunction "VDDCORE_43") (pintype "power_in"))
    )
    (net (code "49") (name "Net-(U2-BST)") (class "Default")
      (node (ref "C4") (pin "1") (pinfunction "1_1") (pintype "passive"))
      (node (ref "U2") (pin "5") (pinfunction "BST_5") (pintype "bidirectional"))
    )
    (net (code "50") (name "Net-(U2-EN{slash}SYNC)") (class "Default")
      (node (ref "R1") (pin "1") (pinfunction "1_1") (pintype "passive"))
      (node (ref "U2") (pin "6") (pinfunction "EN/SYNC_6") (pintype "bidirectional"))
    )
    (net (code "51") (name "Net-(U2-FB)") (class "Default")
      (node (ref "C5") (pin "1") (pinfunction "1_1") (pintype "passive"))
      (node (ref "R2") (pin "2") (pinfunction "2_2") (pintype "passive"))
      (node (ref "R3") (pin "1") (pinfunction "1_1") (pintype "passive"))
      (node (ref "U2") (pin "8") (pinfunction "FB_8") (pintype "bidirectional"))
    )
    (net (code "52") (name "Net-(U2-SW)") (class "Default")
      (node (ref "C4") (pin "2") (pinfunction "2_2") (pintype "passive"))
      (node (ref "L1") (pin "1") (pinfunction "1_1") (pintype "passive"))
      (node (ref "U2") (pin "3") (pinfunction "SW_3") (pintype "bidirectional"))
    )
    (net (code "53") (name "Net-(U2-VCC)") (class "Default")
      (node (ref "C3") (pin "2") (pinfunction "2_2") (pintype "passive"))
      (node (ref "U2") (pin "7") (pinfunction "VCC_7") (pintype "bidirectional"))
    )
    (net (code "54") (name "Net-(U4-CPOUT)") (class "Default")
      (node (ref "C17") (pin "2") (pinfunction "2_2") (pintype "passive"))
      (node (ref "U4") (pin "20") (pinfunction "CPOUT_20") (pintype "passive"))
    )
    (net (code "55") (name "Net-(U4-REGOUT)") (class "Default")
      (node (ref "C15") (pin "2") (pinfunction "2_2") (pintype "passive"))
      (node (ref "U4") (pin "10") (pinfunction "REGOUT_10") (pintype "passive"))
    )
    (net (code "56") (name "Net-(U5-ILIM)") (class "Default")
      (node (ref "R7") (pin "1") (pinfunction "1_1") (pintype "passive"))
      (node (ref "U5") (pin "4") (pinfunction "ILIM_4") (pintype "input"))
    )
    (net (code "57") (name "Net-(U5-OUT1)") (class "Default")
      (node (ref "J2") (pin "1") (pinfunction "1_1") (pintype "passive"))
      (node (ref "U5") (pin "6") (pinfunction "OUT1_6") (pintype "output"))
    )
    (net (code "58") (name "Net-(U5-OUT2)") (class "Default")
      (node (ref "J2") (pin "2") (pinfunction "2_2") (pintype "passive"))
      (node (ref "U5") (pin "8") (pinfunction "OUT2_8") (pintype "output"))
    )
    (net (code "59") (name "Net-(U6-ILIM)") (class "Default")
      (node (ref "R8") (pin "1") (pinfunction "1_1") (pintype "passive"))
      (node (ref "U6") (pin "4") (pinfunction "ILIM_4") (pintype "input"))
    )
    (net (code "60") (name "Net-(U6-OUT1)") (class "Default")
      (node (ref "J3") (pin "1") (pinfunction "1_1") (pintype "passive"))
      (node (ref "U6") (pin "6") (pinfunction "OUT1_6") (pintype "output"))
    )
    (net (code "61") (name "Net-(U6-OUT2)") (class "Default")
      (node (ref "J3") (pin "2") (pinfunction "2_2") (pintype "passive"))
      (node (ref "U6") (pin "8") (pinfunction "OUT2_8") (pintype "output"))
    )
    (net (code "62") (name "Net-(U7-B2)") (class "Default")
      (node (ref "J8") (pin "1") (pinfunction "1_1") (pintype "passive"))
      (node (ref "U7") (pin "12") (pinfunction "B2_12") (pintype "bidirectional"))
    )
    (net (code "63") (name "Net-(U7-B3)") (class "Default")
      (node (ref "J9") (pin "1") (pinfunction "1_1") (pintype "passive"))
      (node (ref "U7") (pin "11") (pinfunction "B3_11") (pintype "bidirectional"))
    )
    (net (code "64") (name "Net-(U7-B4)") (class "Default")
      (node (ref "J10") (pin "1") (pinfunction "1_1") (pintype "passive"))
      (node (ref "U7") (pin "10") (pinfunction "B4_10") (pintype "bidirectional"))
    )
    (net (code "65") (name "RX") (class "Default")
      (node (ref "J17") (pin "P$3") (pinfunction "3_P$3") (pintype "passive"))
      (node (ref "U1") (pin "20") (pinfunction "PB11_20") (pintype "bidirectional"))
    )
    (net (code "66") (name "SCL1") (class "Default")
      (node (ref "J15") (pin "21") (pinfunction "21_21") (pintype "passive"))
      (node (ref "J15") (pin "22") (pinfunction "22_22") (pintype "passive"))
      (node (ref "J6") (pin "1") (pinfunction "1_1") (pintype "passive"))
      (node (ref "R13") (pin "2") (pinfunction "2_2") (pintype "passive"))
      (node (ref "U1") (pin "26") (pinfunction "PA17_26") (pintype "bidirectional"))
    )
    (net (code "67") (name "SCL2") (class "Default")
      (node (ref "J16") (pin "P$2") (pinfunction "2_P$2") (pintype "passive"))
      (node (ref "R15") (pin "2") (pinfunction "2_2") (pintype "passive"))
      (node (ref "U1") (pin "22") (pinfunction "PA13_22") (pintype "bidirectional"))
      (node (ref "U4") (pin "23") (pinfunction "SCL_23") (pintype "input"))
    )
    (net (code "68") (name "SDA1") (class "Default")
      (node (ref "J15") (pin "23") (pinfunction "23_23") (pintype "passive"))
      (node (ref "J15") (pin "24") (pinfunction "24_24") (pintype "passive"))
      (node (ref "J6") (pin "2") (pinfunction "2_2") (pintype "passive"))
      (node (ref "R14") (pin "2") (pinfunction "2_2") (pintype "passive"))
      (node (ref "U1") (pin "25") (pinfunction "PA16_25") (pintype "bidirectional"))
    )
    (net (code "69") (name "SDA2") (class "Default")
      (node (ref "J16") (pin "P$3") (pinfunction "3_P$3") (pintype "passive"))
      (node (ref "R16") (pin "2") (pinfunction "2_2") (pintype "passive"))
      (node (ref "U1") (pin "21") (pinfunction "PA12_21") (pintype "bidirectional"))
      (node (ref "U4") (pin "24") (pinfunction "SDA_24") (pintype "bidirectional"))
    )
    (net (code "70") (name "SERVO1") (class "Default")
      (node (ref "J12") (pin "3") (pinfunction "3_3") (pintype "passive"))
      (node (ref "U1") (pin "1") (pinfunction "PA00_1") (pintype "bidirectional"))
    )
    (net (code "71") (name "SERVO2") (class "Default")
      (node (ref "J12") (pin "6") (pinfunction "6_6") (pintype "passive"))
      (node (ref "U1") (pin "2") (pinfunction "PA01_2") (pintype "bidirectional"))
    )
    (net (code "72") (name "SERVO3") (class "Default")
      (node (ref "J12") (pin "9") (pinfunction "9_9") (pintype "passive"))
      (node (ref "U1") (pin "13") (pinfunction "PA08_13") (pintype "bidirectional"))
    )
    (net (code "73") (name "SERVO4") (class "Default")
      (node (ref "J12") (pin "12") (pinfunction "12_12") (pintype "passive"))
      (node (ref "U1") (pin "14") (pinfunction "PA09_14") (pintype "bidirectional"))
    )
    (net (code "74") (name "SONAR1ECHO") (class "Default")
      (node (ref "U1") (pin "41") (pinfunction "PA28_41") (pintype "bidirectional"))
      (node (ref "U7") (pin "5") (pinfunction "A4_5") (pintype "bidirectional"))
    )
    (net (code "75") (name "SONAR1TRIG") (class "Default")
      (node (ref "J10") (pin "2") (pinfunction "2_2") (pintype "passive"))
      (node (ref "U1") (pin "39") (pinfunction "PA27_39") (pintype "bidirectional"))
    )
    (net (code "76") (name "SONAR2ECHO") (class "Default")
      (node (ref "U1") (pin "47") (pinfunction "PB02_47") (pintype "bidirectional"))
      (node (ref "U7") (pin "4") (pinfunction "A3_4") (pintype "bidirectional"))
    )
    (net (code "77") (name "SONAR2TRIG") (class "Default")
      (node (ref "J9") (pin "2") (pinfunction "2_2") (pintype "passive"))
      (node (ref "U1") (pin "38") (pinfunction "PB23_38") (pintype "bidirectional"))
    )
    (net (code "78") (name "SONAR3ECHO") (class "Default")
      (node (ref "U1") (pin "48") (pinfunction "PB03_48") (pintype "bidirectional"))
      (node (ref "U7") (pin "3") (pinfunction "A2_3") (pintype "bidirectional"))
    )
    (net (code "79") (name "SONAR3TRIG") (class "Default")
      (node (ref "J8") (pin "2") (pinfunction "2_2") (pintype "passive"))
      (node (ref "U1") (pin "37") (pinfunction "PB22_37") (pintype "bidirectional"))
    )
    (net (code "80") (name "SWCLK") (class "Default")
      (node (ref "R11") (pin "2") (pinfunction "2_2") (pintype "passive"))
      (node (ref "TP2") (pin "TP") (pinfunction "TP_TP") (pintype "input"))
      (node (ref "U1") (pin "45") (pinfunction "PA30_45") (pintype "bidirectional"))
    )
    (net (code "81") (name "SWDIO") (class "Default")
      (node (ref "TP3") (pin "TP") (pinfunction "TP_TP") (pintype "input"))
      (node (ref "U1") (pin "46") (pinfunction "PA31_46") (pintype "bidirectional"))
    )
    (net (code "82") (name "TX") (class "Default")
      (node (ref "J17") (pin "P$2") (pinfunction "2_P$2") (pintype "passive"))
      (node (ref "U1") (pin "19") (pinfunction "PB10_19") (pintype "bidirectional"))
    )
    (net (code "83") (name "VSENSE") (class "Default")
      (node (ref "R5") (pin "1") (pinfunction "1_1") (pintype "passive"))
      (node (ref "R6") (pin "1") (pinfunction "1_1") (pintype "passive"))
      (node (ref "U1") (pin "12") (pinfunction "PA07_12") (pintype "bidirectional"))
    )
    (net (code "84") (name "unconnected-(J15-Pad1)") (class "Default")
      (node (ref "J15") (pin "1") (pinfunction "1_1") (pintype "passive"))
    )
    (net (code "85") (name "unconnected-(J15-Pad5)") (class "Default")
      (node (ref "J15") (pin "5") (pinfunction "5_5") (pintype "passive"))
    )
    (net (code "86") (name "unconnected-(J17-4-PadP$4)") (class "Default")
      (node (ref "J17") (pin "P$4") (pinfunction "4_P$4") (pintype "passive"))
    )
    (net (code "87") (name "unconnected-(J17-5-PadP$5)") (class "Default")
      (node (ref "J17") (pin "P$5") (pinfunction "5_P$5") (pintype "passive"))
    )
    (net (code "88") (name "unconnected-(U1-PA03-Pad4)") (class "Default")
      (node (ref "U1") (pin "4") (pinfunction "PA03_4") (pintype "bidirectional"))
    )
    (net (code "89") (name "unconnected-(U1-PA11-Pad16)") (class "Default")
      (node (ref "U1") (pin "16") (pinfunction "PA11_16") (pintype "bidirectional"))
    )
    (net (code "90") (name "unconnected-(U4-AUX_CL-Pad7)") (class "Default")
      (node (ref "U4") (pin "7") (pinfunction "AUX_CL_7") (pintype "input"))
    )
    (net (code "91") (name "unconnected-(U4-AUX_DA-Pad6)") (class "Default")
      (node (ref "U4") (pin "6") (pinfunction "AUX_DA_6") (pintype "bidirectional"))
    )
    (net (code "92") (name "unconnected-(U4-INT-Pad12)") (class "Default")
      (node (ref "U4") (pin "12") (pinfunction "INT_12") (pintype "output"))
    )
    (net (code "93") (name "unconnected-(U4-RESV-Pad19)") (class "Default")
      (node (ref "U4") (pin "19") (pinfunction "RESV_19") (pintype "passive"))
    )
    (net (code "94") (name "unconnected-(U4-RESV-Pad21)") (class "Default")
      (node (ref "U4") (pin "21") (pinfunction "RESV_21") (pintype "passive"))
    )
    (net (code "95") (name "unconnected-(U4-RESV-Pad22)") (class "Default")
      (node (ref "U4") (pin "22") (pinfunction "RESV_22") (pintype "passive"))
    )
    (net (code "96") (name "unconnected-(U7-A1-Pad2)") (class "Default")
      (node (ref "U7") (pin "2") (pinfunction "A1_2") (pintype "bidirectional"))
    )
    (net (code "97") (name "unconnected-(U7-B1-Pad13)") (class "Default")
      (node (ref "U7") (pin "13") (pinfunction "B1_13") (pintype "bidirectional"))
    )
    (net (code "98") (name "unconnected-(U7-NC-Pad9)") (class "Default")
      (node (ref "U7") (pin "9") (pinfunction "NC_9") (pintype "no_connect"))
    )
    (net (code "99") (name "unconnected-(U7-NC_2-Pad6)") (class "Default")
      (node (ref "U7") (pin "6") (pinfunction "NC_2_6") (pintype "no_connect"))
    )
    (net (code "100") (name "unconnected-(USB1-ID-Pad4)") (class "Default")
      (node (ref "USB1") (pin "4") (pinfunction "ID_4") (pintype "bidirectional"))
    )
    (net (code "101") (name "unconnected-(USB1-VCC-Pad1)") (class "Default")
      (node (ref "USB1") (pin "1") (pinfunction "VCC_1") (pintype "bidirectional"))
    )
    (net (code "102") (name "~{RESET}") (class "Default")
      (node (ref "C14") (pin "1") (pinfunction "1_1") (pintype "passive"))
      (node (ref "J14") (pin "1") (pinfunction "1_1") (pintype "passive"))
      (node (ref "J14") (pin "2") (pinfunction "2_2") (pintype "passive"))
      (node (ref "R10") (pin "2") (pinfunction "2_2") (pintype "passive"))
      (node (ref "TP1") (pin "TP") (pinfunction "TP_TP") (pintype "input"))
      (node (ref "U1") (pin "40") (pinfunction "RSTN_40") (pintype "bidirectional"))
    )
  )
)
